# Sheet1.net
KiCad netlist of a schematic drawn in Altium Designer
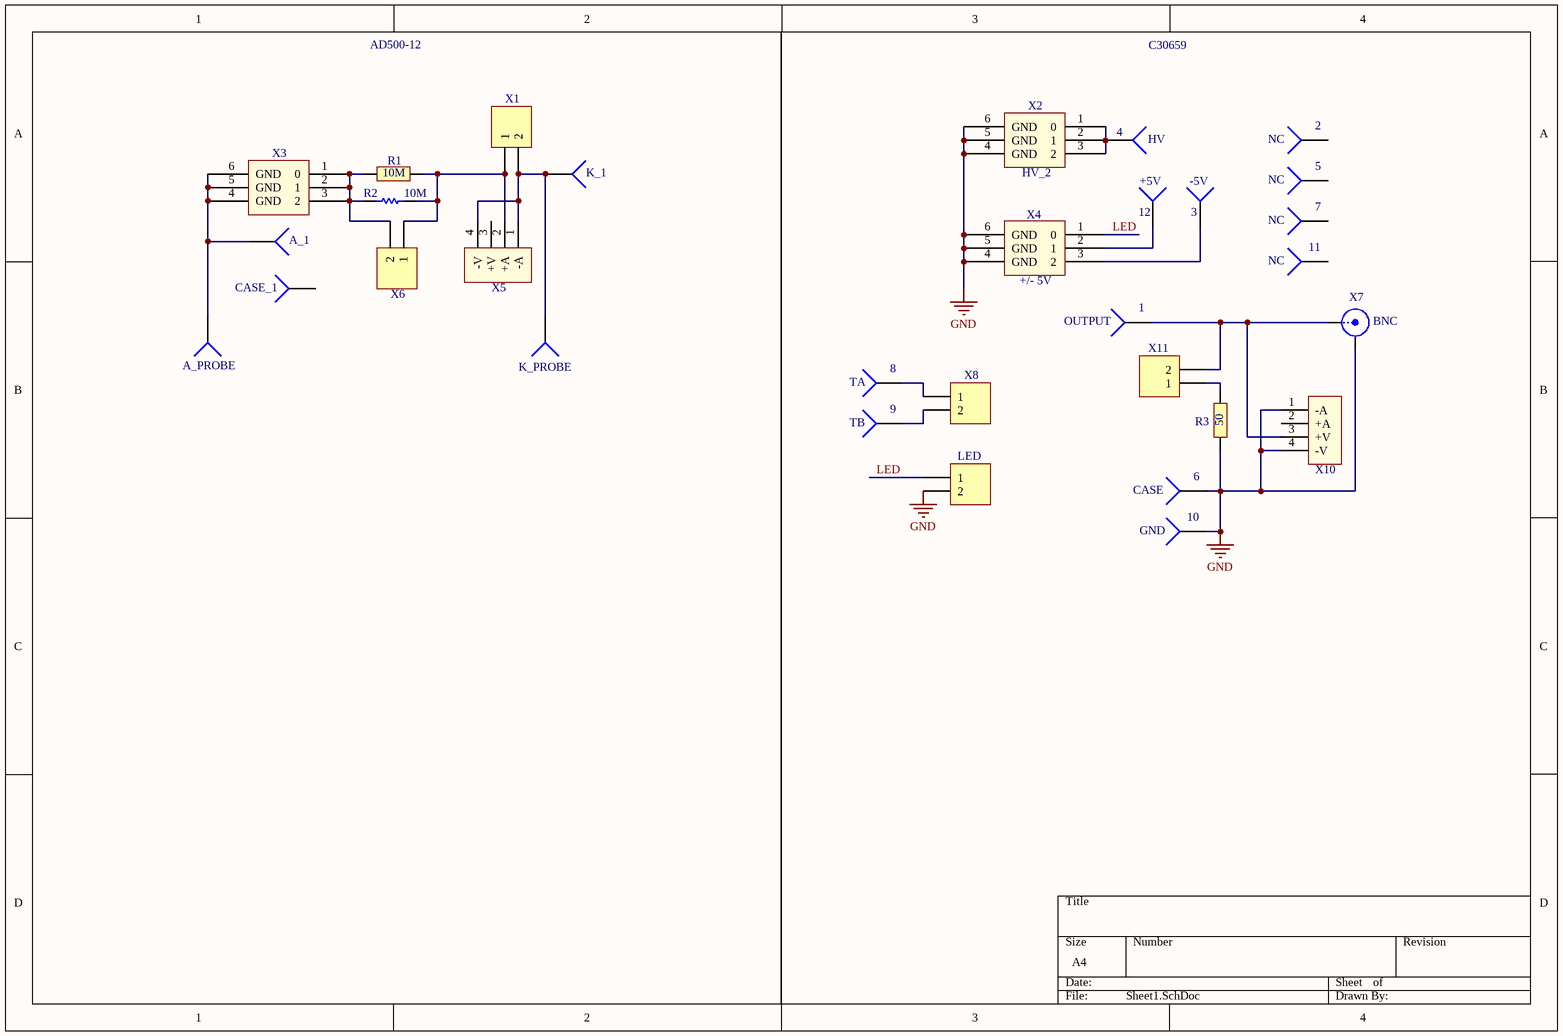
[diagram p0: Sheet1.SchDoc]

(export (version "E")
  (design (tool "Eeschema 10.0.6"))
  (components
    (comp (ref "1")
      (value "OUTPUT")
      (footprint "PIN1")
      (description "Socket")
      (fields (field (name "PUBLISHER") "Altium Limited"))
      (libsource (lib "Miscellaneous Connectors") (part "Socket"))
    )
    (comp (ref "2")
      (value "NC")
      (footprint "PIN1")
      (description "Socket")
      (fields (field (name "PUBLISHER") "Altium Limited"))
      (libsource (lib "Miscellaneous Connectors") (part "Socket"))
    )
    (comp (ref "3")
      (value "-5V")
      (footprint "PIN1")
      (description "Socket")
      (fields (field (name "PUBLISHER") "Altium Limited"))
      (libsource (lib "Miscellaneous Connectors") (part "Socket"))
    )
    (comp (ref "4")
      (value "HV")
      (footprint "PIN1")
      (description "Socket")
      (fields (field (name "PUBLISHER") "Altium Limited"))
      (libsource (lib "Miscellaneous Connectors") (part "Socket"))
    )
    (comp (ref "5")
      (value "NC")
      (footprint "PIN1")
      (description "Socket")
      (fields (field (name "PUBLISHER") "Altium Limited"))
      (libsource (lib "Miscellaneous Connectors") (part "Socket"))
    )
    (comp (ref "6")
      (value "CASE")
      (footprint "PIN1")
      (description "Socket")
      (fields (field (name "PUBLISHER") "Altium Limited"))
      (libsource (lib "Miscellaneous Connectors") (part "Socket"))
    )
    (comp (ref "7")
      (value "NC")
      (footprint "PIN1")
      (description "Socket")
      (fields (field (name "PUBLISHER") "Altium Limited"))
      (libsource (lib "Miscellaneous Connectors") (part "Socket"))
    )
    (comp (ref "8")
      (value "TA")
      (footprint "PIN1")
      (description "Socket")
      (fields (field (name "PUBLISHER") "Altium Limited"))
      (libsource (lib "Miscellaneous Connectors") (part "Socket"))
    )
    (comp (ref "9")
      (value "TB")
      (footprint "PIN1")
      (description "Socket")
      (fields (field (name "PUBLISHER") "Altium Limited"))
      (libsource (lib "Miscellaneous Connectors") (part "Socket"))
    )
    (comp (ref "10")
      (value "GND")
      (footprint "PIN1")
      (description "Socket")
      (fields (field (name "PUBLISHER") "Altium Limited"))
      (libsource (lib "Miscellaneous Connectors") (part "Socket"))
    )
    (comp (ref "11")
      (value "NC")
      (footprint "PIN1")
      (description "Socket")
      (fields (field (name "PUBLISHER") "Altium Limited"))
      (libsource (lib "Miscellaneous Connectors") (part "Socket"))
    )
    (comp (ref "12")
      (value "+5V")
      (footprint "PIN1")
      (description "Socket")
      (fields (field (name "PUBLISHER") "Altium Limited"))
      (libsource (lib "Miscellaneous Connectors") (part "Socket"))
    )
    (comp (ref "A_1")
      (value "Socket")
      (footprint "PIN1")
      (fields (field (name "PUBLISHER") "Altium Limited"))
      (libsource (lib "Miscellaneous Connectors") (part "Socket"))
    )
    (comp (ref "A_PROBE")
      (value "Socket")
      (footprint "PIN1")
      (fields (field (name "PUBLISHER") "Altium Limited"))
      (libsource (lib "Miscellaneous Connectors") (part "Socket"))
    )
    (comp (ref "CASE_1")
      (value "Socket")
      (footprint "PIN1")
      (fields (field (name "PUBLISHER") "Altium Limited"))
      (libsource (lib "Miscellaneous Connectors") (part "Socket"))
    )
    (comp (ref "K_1")
      (value "Socket")
      (footprint "PIN1")
      (fields (field (name "PUBLISHER") "Altium Limited"))
      (libsource (lib "Miscellaneous Connectors") (part "Socket"))
    )
    (comp (ref "K_PROBE")
      (value "Socket")
      (footprint "PIN1")
      (fields (field (name "PUBLISHER") "Altium Limited"))
      (libsource (lib "Miscellaneous Connectors") (part "Socket"))
    )
    (comp (ref "LED")
      (value "Header 2")
      (footprint "HDR1X2")
      (description "Header, 2-Pin")
      (fields (field (name "PUBLISHER") "Altium Limited"))
      (libsource (lib "") (part "Header 2_2"))
    )
    (comp (ref "R1") (value "10M") (footprint "RES") (libsource (lib "") (part "RES_1")))
    (comp (ref "R2")
      (value "10M")
      (footprint "AXIAL-0.3")
      (description "Resistor")
      (fields (field (name "Comment") "Res1") (field (name "PUBLISHER") "Altium Limited"))
      (libsource (lib "Miscellaneous Devices") (part "Res1"))
    )
    (comp (ref "R3") (value "50") (footprint "RES") (libsource (lib "Schlib") (part "RES")))
    (comp (ref "X1")
      (value "Header 2")
      (footprint "HDR1X2")
      (description "Header, 2-Pin")
      (fields (field (name "PUBLISHER") "Altium Limited"))
      (libsource (lib "") (part "Header 2_1"))
    )
    (comp (ref "X2") (value "HV_2") (footprint "POWER") (libsource (lib "Schlib") (part "POWER")))
    (comp (ref "X3") (value "POWER") (footprint "POWER") (libsource (lib "Schlib") (part "POWER")))
    (comp (ref "X4") (value "+/- 5V") (footprint "POWER") (libsource (lib "Schlib") (part "POWER")))
    (comp (ref "X5")
      (value "AMPVOLT")
      (footprint "AMP_VOLTMETER")
      (libsource (lib "") (part "AMP_VOLTMETER_1"))
    )
    (comp (ref "X6")
      (value "Header 2")
      (footprint "HDR1X2")
      (description "Header, 2-Pin")
      (fields (field (name "PUBLISHER") "Altium Limited"))
      (libsource (lib "") (part "Header 2_3"))
    )
    (comp (ref "X7")
      (value "BNC")
      (footprint "BNC_RA CON")
      (description "BNC Elbow Connector")
      (fields (field (name "PUBLISHER") "Altium Limited"))
      (libsource (lib "Miscellaneous Connectors") (part "BNC"))
    )
    (comp (ref "X8")
      (value "Header 2")
      (footprint "HDR1X2")
      (description "Header, 2-Pin")
      (fields (field (name "PUBLISHER") "Altium Limited"))
      (libsource (lib "") (part "Header 2_2"))
    )
    (comp (ref "X10")
      (value "AMPVOLT")
      (footprint "AMP_VOLTMETER")
      (libsource (lib "Schlib") (part "AMP_VOLTMETER"))
    )
    (comp (ref "X11")
      (value "Header 2")
      (footprint "HDR1X2")
      (description "Header, 2-Pin")
      (fields (field (name "PUBLISHER") "Altium Limited"))
      (libsource (lib "Miscellaneous Connectors") (part "Header 2"))
    )
  )
  (nets
    (net (code "1") (name "/LED") (class "Default")
      (node (ref "LED") (pin "1") (pinfunction "1_1") (pintype "passive"))
      (node (ref "X4") (pin "1") (pinfunction "0_1") (pintype "passive"))
    )
    (net (code "2") (name "GND") (class "Default")
      (node (ref "10") (pin "1") (pinfunction "1_1") (pintype "passive"))
      (node (ref "6") (pin "1") (pinfunction "1_1") (pintype "passive"))
      (node (ref "LED") (pin "2") (pinfunction "2_2") (pintype "passive"))
      (node (ref "R3") (pin "1") (pinfunction "1_1") (pintype "passive"))
      (node (ref "X10") (pin "1") (pinfunction "-A_1") (pintype "passive"))
      (node (ref "X10") (pin "4") (pinfunction "-V_4") (pintype "passive"))
      (node (ref "X2") (pin "4") (pinfunction "GND_4") (pintype "passive"))
      (node (ref "X2") (pin "5") (pinfunction "GND_5") (pintype "passive"))
      (node (ref "X2") (pin "6") (pinfunction "GND_6") (pintype "passive"))
      (node (ref "X4") (pin "4") (pinfunction "GND_4") (pintype "passive"))
      (node (ref "X4") (pin "5") (pinfunction "GND_5") (pintype "passive"))
      (node (ref "X4") (pin "6") (pinfunction "GND_6") (pintype "passive"))
      (node (ref "X7") (pin "2") (pinfunction "Y_2") (pintype "passive"))
    )
    (net (code "3") (name "Net-(8-Pad1)") (class "Default")
      (node (ref "8") (pin "1") (pinfunction "1_1") (pintype "passive"))
      (node (ref "X8") (pin "1") (pinfunction "1_1") (pintype "passive"))
    )
    (net (code "4") (name "Net-(9-Pad1)") (class "Default")
      (node (ref "9") (pin "1") (pinfunction "1_1") (pintype "passive"))
      (node (ref "X8") (pin "2") (pinfunction "2_2") (pintype "passive"))
    )
    (net (code "5") (name "Net-(A_1-Pad1)") (class "Default")
      (node (ref "A_1") (pin "1") (pinfunction "1_1") (pintype "passive"))
      (node (ref "A_PROBE") (pin "1") (pinfunction "1_1") (pintype "passive"))
      (node (ref "X3") (pin "4") (pinfunction "GND_4") (pintype "passive"))
      (node (ref "X3") (pin "5") (pinfunction "GND_5") (pintype "passive"))
      (node (ref "X3") (pin "6") (pinfunction "GND_6") (pintype "passive"))
    )
    (net (code "6") (name "Net-(R3-Pad2)") (class "Default")
      (node (ref "R3") (pin "2") (pinfunction "2_2") (pintype "passive"))
      (node (ref "X11") (pin "1") (pinfunction "1_1") (pintype "passive"))
    )
    (net (code "7") (name "Net-(X2-0)") (class "Default")
      (node (ref "4") (pin "1") (pinfunction "1_1") (pintype "passive"))
      (node (ref "X2") (pin "1") (pinfunction "0_1") (pintype "passive"))
      (node (ref "X2") (pin "2") (pinfunction "1_2") (pintype "passive"))
      (node (ref "X2") (pin "3") (pinfunction "2_3") (pintype "passive"))
    )
    (net (code "8") (name "Net-(X3-0)") (class "Default")
      (node (ref "R1") (pin "1") (pinfunction "1_1") (pintype "passive"))
      (node (ref "R2") (pin "1") (pinfunction "1_1") (pintype "passive"))
      (node (ref "X3") (pin "1") (pinfunction "0_1") (pintype "passive"))
      (node (ref "X3") (pin "2") (pinfunction "1_2") (pintype "passive"))
      (node (ref "X3") (pin "3") (pinfunction "2_3") (pintype "passive"))
      (node (ref "X6") (pin "2") (pinfunction "2_2") (pintype "passive"))
    )
    (net (code "9") (name "Net-(X4-1)") (class "Default")
      (node (ref "12") (pin "1") (pinfunction "1_1") (pintype "passive"))
      (node (ref "X4") (pin "2") (pinfunction "1_2") (pintype "passive"))
    )
    (net (code "10") (name "Net-(X4-2)") (class "Default")
      (node (ref "3") (pin "1") (pinfunction "1_1") (pintype "passive"))
      (node (ref "X4") (pin "3") (pinfunction "2_3") (pintype "passive"))
    )
    (net (code "11") (name "Net-(X5-+A)") (class "Default")
      (node (ref "R1") (pin "2") (pinfunction "2_2") (pintype "passive"))
      (node (ref "R2") (pin "2") (pinfunction "2_2") (pintype "passive"))
      (node (ref "X1") (pin "1") (pinfunction "1_1") (pintype "passive"))
      (node (ref "X5") (pin "2") (pinfunction "+A_2") (pintype "passive"))
      (node (ref "X6") (pin "1") (pinfunction "1_1") (pintype "passive"))
    )
    (net (code "12") (name "Net-(X5--A)") (class "Default")
      (node (ref "K_1") (pin "1") (pinfunction "1_1") (pintype "passive"))
      (node (ref "K_PROBE") (pin "1") (pinfunction "1_1") (pintype "passive"))
      (node (ref "X1") (pin "2") (pinfunction "2_2") (pintype "passive"))
      (node (ref "X5") (pin "1") (pinfunction "-A_1") (pintype "passive"))
      (node (ref "X5") (pin "4") (pinfunction "-V_4") (pintype "passive"))
    )
    (net (code "13") (name "Net-(X10-+V)") (class "Default")
      (node (ref "1") (pin "1") (pinfunction "1_1") (pintype "passive"))
      (node (ref "X10") (pin "3") (pinfunction "+V_3") (pintype "passive"))
      (node (ref "X11") (pin "2") (pinfunction "2_2") (pintype "passive"))
      (node (ref "X7") (pin "1") (pinfunction "X_1") (pintype "passive"))
    )
    (net (code "14") (name "unconnected-(2-Pad1)") (class "Default")
      (node (ref "2") (pin "1") (pinfunction "1_1") (pintype "passive"))
    )
    (net (code "15") (name "unconnected-(5-Pad1)") (class "Default")
      (node (ref "5") (pin "1") (pinfunction "1_1") (pintype "passive"))
    )
    (net (code "16") (name "unconnected-(7-Pad1)") (class "Default")
      (node (ref "7") (pin "1") (pinfunction "1_1") (pintype "passive"))
    )
    (net (code "17") (name "unconnected-(11-Pad1)") (class "Default")
      (node (ref "11") (pin "1") (pinfunction "1_1") (pintype "passive"))
    )
    (net (code "18") (name "unconnected-(CASE_1-Pad1)") (class "Default")
      (node (ref "CASE_1") (pin "1") (pinfunction "1_1") (pintype "passive"))
    )
    (net (code "19") (name "unconnected-(X5-+V-Pad3)") (class "Default")
      (node (ref "X5") (pin "3") (pinfunction "+V_3") (pintype "passive"))
    )
    (net (code "20") (name "unconnected-(X10-+A-Pad2)") (class "Default")
      (node (ref "X10") (pin "2") (pinfunction "+A_2") (pintype "passive"))
    )
  )
)
